# MCU.net
KiCad netlist of a schematic drawn in Altium Designer
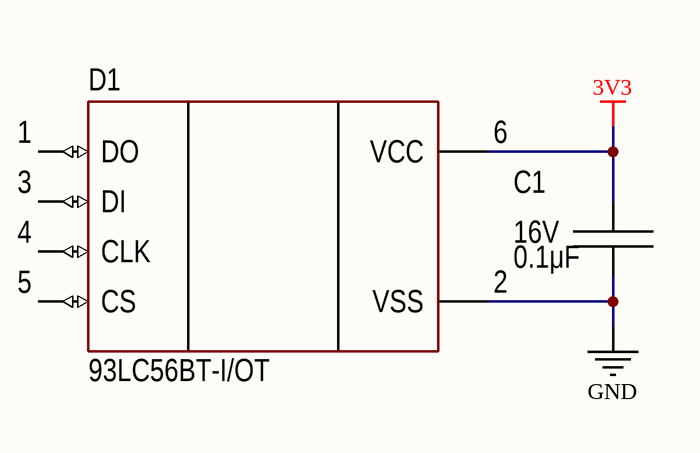
[diagram p0: MCU.SchDoc]

(export (version "E")
  (design (tool "Eeschema 10.0.6"))
  (components
    (comp (ref "C1")
      (value "0.1μF")
      (footprint "CAP: 0805")
      (fields
        (field (name "MANUFACTURER") "Yageo")
        (field (name "PARTNUMBER") "CC0805KRX7R7BB104")
        (field (name "VALUEMANUFACTURERPARTNUMBER") "Ceramic capacitor, 0.1μF, X7R, ±10%, 16V, 0805, -55...+125°C")
        (field (name "VOLTAGE") "16V")
      )
      (libsource (lib "capacitor") (part "Ceramic_0805"))
    )
    (comp (ref "D1")
      (value "~")
      (footprint "SOT23-6")
      (description "EEPROM")
      (fields
        (field (name "MANUFACTURER") "Microchip Technology")
        (field (name "VALUEMANUFACTURERPARTNUMBER") "IC memory, EEPROM, 2KB (256x8), 2 MHz, SPI, 2.5...5.5V, -40...+85°C, SOT-23-6")
        (field (name "PARTNUMBER") "93LC56BT-I/OT")
      )
      (libsource (lib "ic-memory") (part "93LC56BT"))
    )
  )
  (nets
    (net (code "1") (name "3V3") (class "Default")
      (node (ref "C1") (pin "2") (pinfunction "2_2") (pintype "passive"))
      (node (ref "D1") (pin "6") (pinfunction "VCC_6") (pintype "power_in"))
    )
    (net (code "2") (name "GND") (class "Default")
      (node (ref "C1") (pin "1") (pinfunction "1_1") (pintype "passive"))
      (node (ref "D1") (pin "2") (pinfunction "VSS_2") (pintype "power_in"))
    )
    (net (code "3") (name "unconnected-(D1-CLK-Pad4)") (class "Default")
      (node (ref "D1") (pin "4") (pinfunction "CLK_4") (pintype "bidirectional"))
    )
    (net (code "4") (name "unconnected-(D1-CS-Pad5)") (class "Default")
      (node (ref "D1") (pin "5") (pinfunction "CS_5") (pintype "bidirectional"))
    )
    (net (code "5") (name "unconnected-(D1-DI-Pad3)") (class "Default")
      (node (ref "D1") (pin "3") (pinfunction "DI_3") (pintype "bidirectional"))
    )
    (net (code "6") (name "unconnected-(D1-DO-Pad1)") (class "Default")
      (node (ref "D1") (pin "1") (pinfunction "DO_1") (pintype "bidirectional"))
    )
  )
)
